# INTERFACE_PWR_LS_HS.net
KiCad netlist of a schematic drawn in Altium Designer
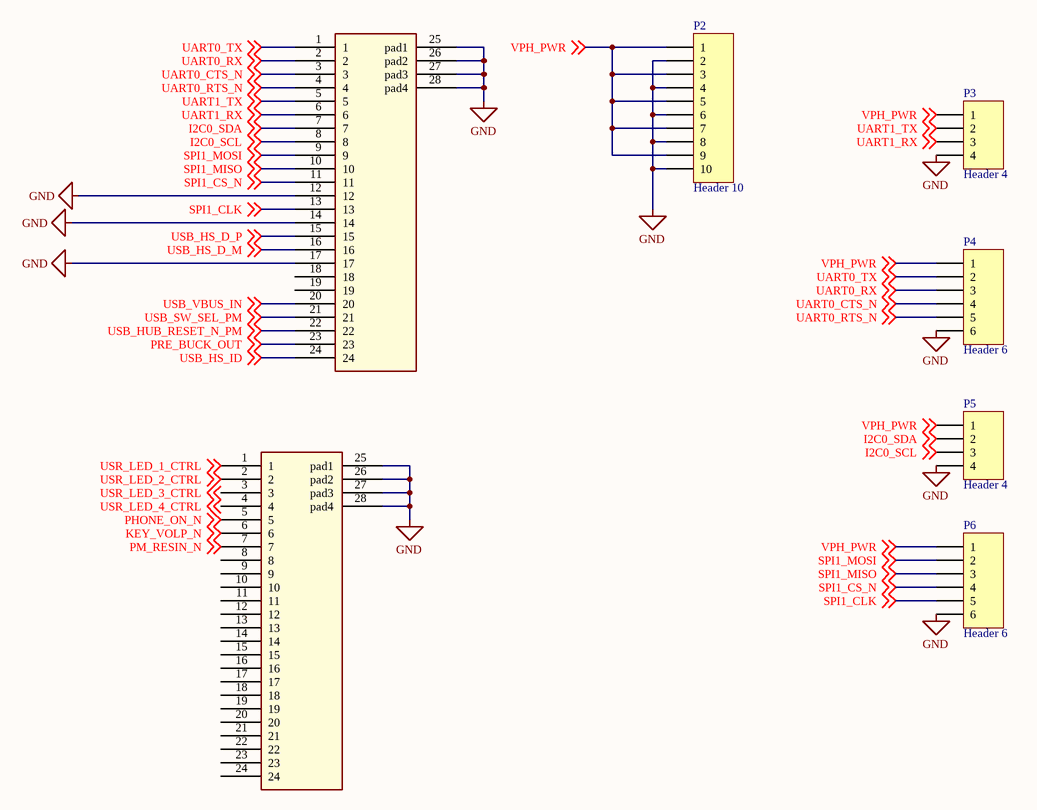
[diagram p0: INTERFACE_PWR_LS_HS.SchDoc]

(export (version "E")
  (design (tool "Eeschema 10.0.6"))
  (components
    (comp (ref "CN1") (value "CON24_0") (libsource (lib "MSM8916_DRAM_PMIC_REF_Library") (part "CON24_0")))
    (comp (ref "CN2") (value "CON24_0") (libsource (lib "MSM8916_DRAM_PMIC_REF_Library") (part "CON24_0")))
    (comp (ref "P2")
      (value "Header 10")
      (footprint "HDR1X10")
      (description "Header, 10-Pin")
      (fields (field (name "PUBLISHER") "Altium Limited"))
      (libsource (lib "Miscellaneous Connectors") (part "Header 10"))
    )
    (comp (ref "P3")
      (value "Header 4")
      (footprint "HDR1X4")
      (description "Header, 4-Pin")
      (fields (field (name "PUBLISHER") "Altium Limited"))
      (libsource (lib "Miscellaneous Connectors") (part "Header 4"))
    )
    (comp (ref "P4")
      (value "Header 6")
      (footprint "HDR1X6")
      (description "Header, 6-Pin")
      (fields (field (name "PUBLISHER") "Altium Limited"))
      (libsource (lib "Miscellaneous Connectors") (part "Header 6"))
    )
    (comp (ref "P5")
      (value "Header 4")
      (footprint "HDR1X4")
      (description "Header, 4-Pin")
      (fields (field (name "PUBLISHER") "Altium Limited"))
      (libsource (lib "Miscellaneous Connectors") (part "Header 4"))
    )
    (comp (ref "P6")
      (value "Header 6")
      (footprint "HDR1X6")
      (description "Header, 6-Pin")
      (fields (field (name "PUBLISHER") "Altium Limited"))
      (libsource (lib "Miscellaneous Connectors") (part "Header 6"))
    )
  )
  (nets
    (net (code "1") (name "GND") (class "Default")
      (node (ref "CN1") (pin "12") (pinfunction "12_12") (pintype "passive"))
      (node (ref "CN1") (pin "14") (pinfunction "14_14") (pintype "passive"))
      (node (ref "CN1") (pin "17") (pinfunction "17_17") (pintype "passive"))
      (node (ref "CN1") (pin "25") (pinfunction "pad1_25") (pintype "passive"))
      (node (ref "CN1") (pin "26") (pinfunction "pad2_26") (pintype "passive"))
      (node (ref "CN1") (pin "27") (pinfunction "pad3_27") (pintype "passive"))
      (node (ref "CN1") (pin "28") (pinfunction "pad4_28") (pintype "passive"))
      (node (ref "CN2") (pin "25") (pinfunction "pad1_25") (pintype "passive"))
      (node (ref "CN2") (pin "26") (pinfunction "pad2_26") (pintype "passive"))
      (node (ref "CN2") (pin "27") (pinfunction "pad3_27") (pintype "passive"))
      (node (ref "CN2") (pin "28") (pinfunction "pad4_28") (pintype "passive"))
      (node (ref "P2") (pin "10") (pinfunction "10_10") (pintype "passive"))
      (node (ref "P2") (pin "2") (pinfunction "2_2") (pintype "passive"))
      (node (ref "P2") (pin "4") (pinfunction "4_4") (pintype "passive"))
      (node (ref "P2") (pin "6") (pinfunction "6_6") (pintype "passive"))
      (node (ref "P2") (pin "8") (pinfunction "8_8") (pintype "passive"))
      (node (ref "P3") (pin "4") (pinfunction "4_4") (pintype "passive"))
      (node (ref "P4") (pin "6") (pinfunction "6_6") (pintype "passive"))
      (node (ref "P5") (pin "4") (pinfunction "4_4") (pintype "passive"))
      (node (ref "P6") (pin "6") (pinfunction "6_6") (pintype "passive"))
    )
    (net (code "2") (name "I2C0_SCL") (class "Default")
      (node (ref "CN1") (pin "8") (pinfunction "8_8") (pintype "passive"))
      (node (ref "P5") (pin "3") (pinfunction "3_3") (pintype "passive"))
    )
    (net (code "3") (name "I2C0_SDA") (class "Default")
      (node (ref "CN1") (pin "7") (pinfunction "7_7") (pintype "passive"))
      (node (ref "P5") (pin "2") (pinfunction "2_2") (pintype "passive"))
    )
    (net (code "4") (name "KEY_VOLP_N") (class "Default")
      (node (ref "CN2") (pin "6") (pinfunction "6_6") (pintype "passive"))
    )
    (net (code "5") (name "PHONE_ON_N") (class "Default")
      (node (ref "CN2") (pin "5") (pinfunction "5_5") (pintype "passive"))
    )
    (net (code "6") (name "PM_RESIN_N") (class "Default")
      (node (ref "CN2") (pin "7") (pinfunction "7_7") (pintype "passive"))
    )
    (net (code "7") (name "PRE_BUCK_OUT") (class "Default")
      (node (ref "CN1") (pin "23") (pinfunction "23_23") (pintype "passive"))
    )
    (net (code "8") (name "SPI1_CLK") (class "Default")
      (node (ref "CN1") (pin "13") (pinfunction "13_13") (pintype "passive"))
      (node (ref "P6") (pin "5") (pinfunction "5_5") (pintype "passive"))
    )
    (net (code "9") (name "SPI1_CS_N") (class "Default")
      (node (ref "CN1") (pin "11") (pinfunction "11_11") (pintype "passive"))
      (node (ref "P6") (pin "4") (pinfunction "4_4") (pintype "passive"))
    )
    (net (code "10") (name "SPI1_MISO") (class "Default")
      (node (ref "CN1") (pin "10") (pinfunction "10_10") (pintype "passive"))
      (node (ref "P6") (pin "3") (pinfunction "3_3") (pintype "passive"))
    )
    (net (code "11") (name "SPI1_MOSI") (class "Default")
      (node (ref "CN1") (pin "9") (pinfunction "9_9") (pintype "passive"))
      (node (ref "P6") (pin "2") (pinfunction "2_2") (pintype "passive"))
    )
    (net (code "12") (name "UART0_CTS_N") (class "Default")
      (node (ref "CN1") (pin "3") (pinfunction "3_3") (pintype "passive"))
      (node (ref "P4") (pin "4") (pinfunction "4_4") (pintype "passive"))
    )
    (net (code "13") (name "UART0_RTS_N") (class "Default")
      (node (ref "CN1") (pin "4") (pinfunction "4_4") (pintype "passive"))
      (node (ref "P4") (pin "5") (pinfunction "5_5") (pintype "passive"))
    )
    (net (code "14") (name "UART0_RX") (class "Default")
      (node (ref "CN1") (pin "2") (pinfunction "2_2") (pintype "passive"))
      (node (ref "P4") (pin "3") (pinfunction "3_3") (pintype "passive"))
    )
    (net (code "15") (name "UART0_TX") (class "Default")
      (node (ref "CN1") (pin "1") (pinfunction "1_1") (pintype "passive"))
      (node (ref "P4") (pin "2") (pinfunction "2_2") (pintype "passive"))
    )
    (net (code "16") (name "UART1_RX") (class "Default")
      (node (ref "CN1") (pin "6") (pinfunction "6_6") (pintype "passive"))
      (node (ref "P3") (pin "3") (pinfunction "3_3") (pintype "passive"))
    )
    (net (code "17") (name "UART1_TX") (class "Default")
      (node (ref "CN1") (pin "5") (pinfunction "5_5") (pintype "passive"))
      (node (ref "P3") (pin "2") (pinfunction "2_2") (pintype "passive"))
    )
    (net (code "18") (name "USB_HS_D_M") (class "Default")
      (node (ref "CN1") (pin "16") (pinfunction "16_16") (pintype "passive"))
    )
    (net (code "19") (name "USB_HS_D_P") (class "Default")
      (node (ref "CN1") (pin "15") (pinfunction "15_15") (pintype "passive"))
    )
    (net (code "20") (name "USB_HS_ID") (class "Default")
      (node (ref "CN1") (pin "24") (pinfunction "24_24") (pintype "passive"))
    )
    (net (code "21") (name "USB_HUB_RESET_N_PM") (class "Default")
      (node (ref "CN1") (pin "22") (pinfunction "22_22") (pintype "passive"))
    )
    (net (code "22") (name "USB_SW_SEL_PM") (class "Default")
      (node (ref "CN1") (pin "21") (pinfunction "21_21") (pintype "passive"))
    )
    (net (code "23") (name "USB_VBUS_IN") (class "Default")
      (node (ref "CN1") (pin "20") (pinfunction "20_20") (pintype "passive"))
    )
    (net (code "24") (name "USR_LED_1_CTRL") (class "Default")
      (node (ref "CN2") (pin "1") (pinfunction "1_1") (pintype "passive"))
    )
    (net (code "25") (name "USR_LED_2_CTRL") (class "Default")
      (node (ref "CN2") (pin "2") (pinfunction "2_2") (pintype "passive"))
    )
    (net (code "26") (name "USR_LED_3_CTRL") (class "Default")
      (node (ref "CN2") (pin "3") (pinfunction "3_3") (pintype "passive"))
    )
    (net (code "27") (name "USR_LED_4_CTRL") (class "Default")
      (node (ref "CN2") (pin "4") (pinfunction "4_4") (pintype "passive"))
    )
    (net (code "28") (name "VPH_PWR") (class "Default")
      (node (ref "P2") (pin "1") (pinfunction "1_1") (pintype "passive"))
      (node (ref "P2") (pin "3") (pinfunction "3_3") (pintype "passive"))
      (node (ref "P2") (pin "5") (pinfunction "5_5") (pintype "passive"))
      (node (ref "P2") (pin "7") (pinfunction "7_7") (pintype "passive"))
      (node (ref "P2") (pin "9") (pinfunction "9_9") (pintype "passive"))
      (node (ref "P3") (pin "1") (pinfunction "1_1") (pintype "passive"))
      (node (ref "P4") (pin "1") (pinfunction "1_1") (pintype "passive"))
      (node (ref "P5") (pin "1") (pinfunction "1_1") (pintype "passive"))
      (node (ref "P6") (pin "1") (pinfunction "1_1") (pintype "passive"))
    )
    (net (code "29") (name "unconnected-(CN1-Pad18)") (class "Default")
      (node (ref "CN1") (pin "18") (pinfunction "18_18") (pintype "passive"))
    )
    (net (code "30") (name "unconnected-(CN1-Pad19)") (class "Default")
      (node (ref "CN1") (pin "19") (pinfunction "19_19") (pintype "passive"))
    )
    (net (code "31") (name "unconnected-(CN2-Pad8)") (class "Default")
      (node (ref "CN2") (pin "8") (pinfunction "8_8") (pintype "passive"))
    )
    (net (code "32") (name "unconnected-(CN2-Pad9)") (class "Default")
      (node (ref "CN2") (pin "9") (pinfunction "9_9") (pintype "passive"))
    )
    (net (code "33") (name "unconnected-(CN2-Pad10)") (class "Default")
      (node (ref "CN2") (pin "10") (pinfunction "10_10") (pintype "passive"))
    )
    (net (code "34") (name "unconnected-(CN2-Pad11)") (class "Default")
      (node (ref "CN2") (pin "11") (pinfunction "11_11") (pintype "passive"))
    )
    (net (code "35") (name "unconnected-(CN2-Pad12)") (class "Default")
      (node (ref "CN2") (pin "12") (pinfunction "12_12") (pintype "passive"))
    )
    (net (code "36") (name "unconnected-(CN2-Pad13)") (class "Default")
      (node (ref "CN2") (pin "13") (pinfunction "13_13") (pintype "passive"))
    )
    (net (code "37") (name "unconnected-(CN2-Pad14)") (class "Default")
      (node (ref "CN2") (pin "14") (pinfunction "14_14") (pintype "passive"))
    )
    (net (code "38") (name "unconnected-(CN2-Pad15)") (class "Default")
      (node (ref "CN2") (pin "15") (pinfunction "15_15") (pintype "passive"))
    )
    (net (code "39") (name "unconnected-(CN2-Pad16)") (class "Default")
      (node (ref "CN2") (pin "16") (pinfunction "16_16") (pintype "passive"))
    )
    (net (code "40") (name "unconnected-(CN2-Pad17)") (class "Default")
      (node (ref "CN2") (pin "17") (pinfunction "17_17") (pintype "passive"))
    )
    (net (code "41") (name "unconnected-(CN2-Pad18)") (class "Default")
      (node (ref "CN2") (pin "18") (pinfunction "18_18") (pintype "passive"))
    )
    (net (code "42") (name "unconnected-(CN2-Pad19)") (class "Default")
      (node (ref "CN2") (pin "19") (pinfunction "19_19") (pintype "passive"))
    )
    (net (code "43") (name "unconnected-(CN2-Pad20)") (class "Default")
      (node (ref "CN2") (pin "20") (pinfunction "20_20") (pintype "passive"))
    )
    (net (code "44") (name "unconnected-(CN2-Pad21)") (class "Default")
      (node (ref "CN2") (pin "21") (pinfunction "21_21") (pintype "passive"))
    )
    (net (code "45") (name "unconnected-(CN2-Pad22)") (class "Default")
      (node (ref "CN2") (pin "22") (pinfunction "22_22") (pintype "passive"))
    )
    (net (code "46") (name "unconnected-(CN2-Pad23)") (class "Default")
      (node (ref "CN2") (pin "23") (pinfunction "23_23") (pintype "passive"))
    )
    (net (code "47") (name "unconnected-(CN2-Pad24)") (class "Default")
      (node (ref "CN2") (pin "24") (pinfunction "24_24") (pintype "passive"))
    )
  )
)
